# intf_conn_pwr.net
KiCad netlist of a schematic drawn in Altium Designer
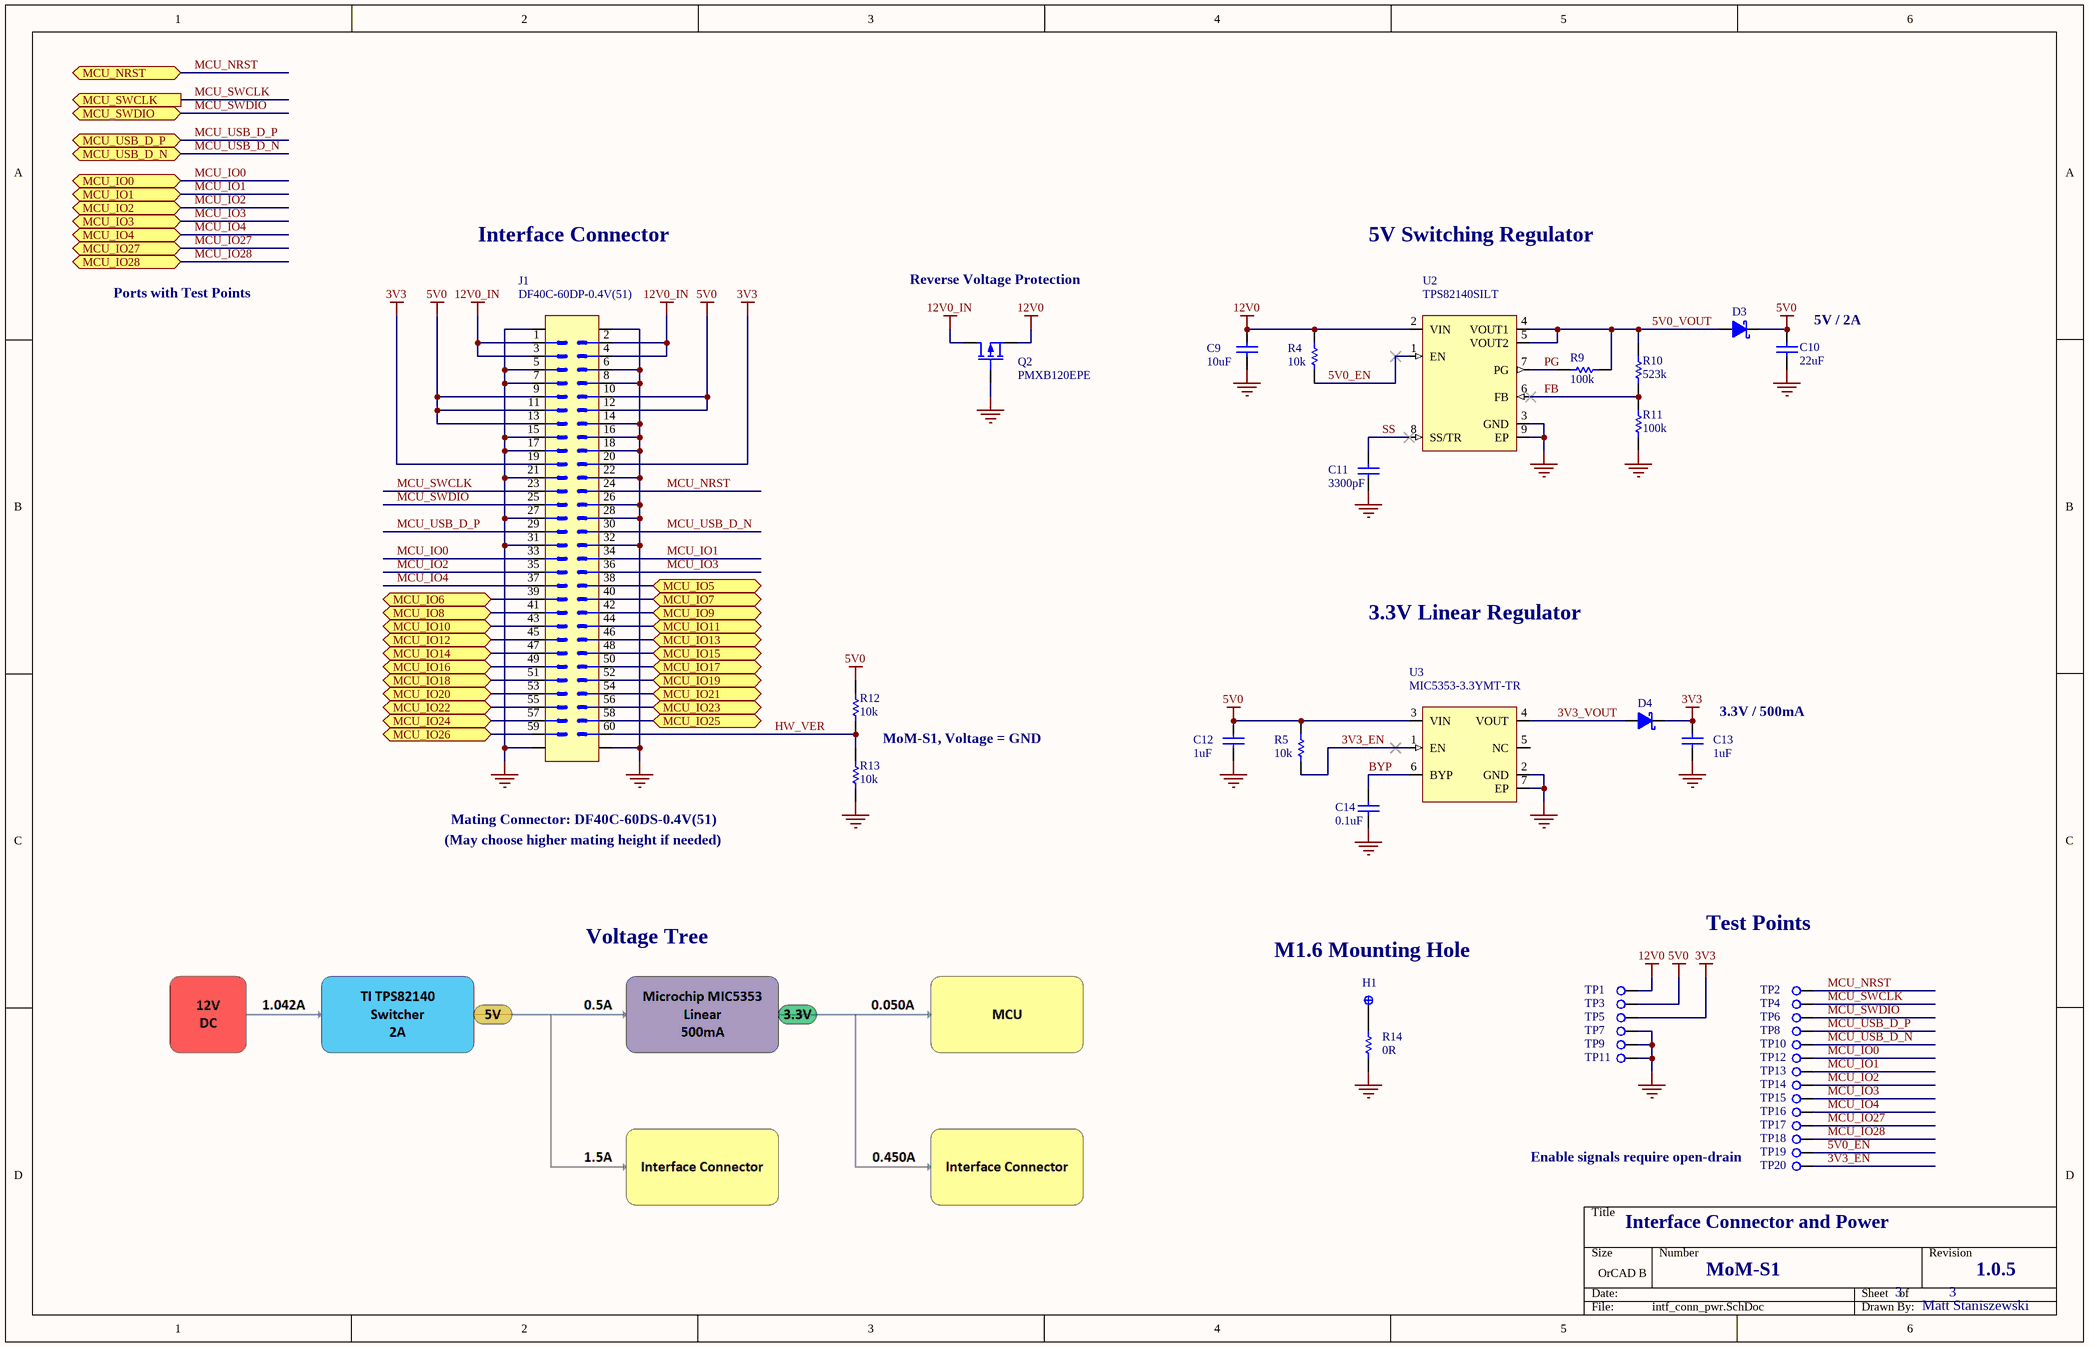
[diagram p0: intf_conn_pwr.SchDoc]

(export (version "E")
  (design (tool "Eeschema 10.0.6"))
  (components
    (comp (ref "C9")
      (value "10uF")
      (footprint "C0603")
      (description "CAP CER 10UF 25V X5R 0603")
      (fields
        (field (name "MANUFACTURER") "Murata")
        (field (name "MANUFACTURER PART NUMBER") "GRM188R61E106MA73D")
      )
      (libsource (lib "Capacitors") (part "10uF 25V 0603"))
    )
    (comp (ref "C10")
      (value "22uF")
      (footprint "C0603")
      (description "CAP CER 22UF 16V X5R 0603")
      (fields
        (field (name "MANUFACTURER") "Samsung")
        (field (name "MANUFACTURER PART NUMBER") "CL10A226MO7JZNC")
      )
      (libsource (lib "Capacitors") (part "22uF 16V 0603"))
    )
    (comp (ref "C11")
      (value "3300pF")
      (footprint "C0201")
      (description "CAP CER 3300PF 16V X7R 0201")
      (fields
        (field (name "MANUFACTURER") "Murata")
        (field (name "MANUFACTURER PART NUMBER") "GRM033R71C332KA88D")
      )
      (libsource (lib "Capacitors") (part "3300pF 16V 0201"))
    )
    (comp (ref "C12")
      (value "1uF")
      (footprint "C0402")
      (description "CAP CER 1UF 25V X5R 0402")
      (fields
        (field (name "MANUFACTURER") "Taiyo Yuden")
        (field (name "MANUFACTURER PART NUMBER") "TMK105BJ105MV-F")
      )
      (libsource (lib "Capacitors") (part "1uF 25V 0402"))
    )
    (comp (ref "C13")
      (value "1uF")
      (footprint "C0402")
      (description "CAP CER 1UF 25V X5R 0402")
      (fields
        (field (name "MANUFACTURER") "Taiyo Yuden")
        (field (name "MANUFACTURER PART NUMBER") "TMK105BJ105MV-F")
      )
      (libsource (lib "Capacitors") (part "1uF 25V 0402"))
    )
    (comp (ref "C14")
      (value "0.1uF")
      (footprint "C0201")
      (description "CAP CER 0.1UF 16V X5R 0201")
      (fields
        (field (name "MANUFACTURER") "Murata")
        (field (name "MANUFACTURER PART NUMBER") "GRM033R61C104ME84D")
      )
      (libsource (lib "Capacitors") (part "0.1uF 16V 0201"))
    )
    (comp (ref "D3")
      (value "SDM2U30CSP-7")
      (footprint "DIO_X3-WLB1608-2")
      (description "DIODE SCHTKY 30V 2A X3-WLB1608-2")
      (fields (field (name "MANUFACTURER") "Diodes"))
      (libsource (lib "Diodes") (part "SDM2U30CSP-7"))
    )
    (comp (ref "D4")
      (value "SDM2U30CSP-7")
      (footprint "DIO_X3-WLB1608-2")
      (description "DIODE SCHTKY 30V 2A X3-WLB1608-2")
      (fields (field (name "MANUFACTURER") "Diodes"))
      (libsource (lib "Diodes") (part "SDM2U30CSP-7"))
    )
    (comp (ref "H1")
      (value "M1.6 MNT HOLE")
      (footprint "MNT_HOLE_M1.6")
      (description "M1.6 Mounting Hole")
      (libsource (lib "Misc") (part "M1.6 MNT HOLE"))
    )
    (comp (ref "J1")
      (value "DF40C-60DP-0.4V(51)")
      (footprint "HRS_DF40C_60P_PLG")
      (description "CONN HDR 60POS 0.4MM SMD GOLD")
      (fields (field (name "MANUFACTURER") "Hirose"))
      (libsource (lib "Connectors") (part "60P 0.4mm Hirose Conn Plug"))
    )
    (comp (ref "Q2")
      (value "PMXB120EPE")
      (footprint "NXP_DFN1010D-3")
      (description "MOSFET P-CH 30V 2.4A 3DFN")
      (fields (field (name "MANUFACTURER") "NXP Semiconductors"))
      (libsource (lib "ICs") (part "PMXB120EPE"))
    )
    (comp (ref "R4")
      (value "10k")
      (footprint "R0201")
      (description "RES SMD 10K OHM 1% 1/20W 0201")
      (fields
        (field (name "MANUFACTURER") "Panasonic ECG")
        (field (name "MANUFACTURER PART NUMBER") "ERJ-1GEF1002C")
      )
      (libsource (lib "Resistors") (part "10k 0201"))
    )
    (comp (ref "R5")
      (value "10k")
      (footprint "R0201")
      (description "RES SMD 10K OHM 1% 1/20W 0201")
      (fields
        (field (name "MANUFACTURER") "Panasonic ECG")
        (field (name "MANUFACTURER PART NUMBER") "ERJ-1GEF1002C")
      )
      (libsource (lib "Resistors") (part "10k 0201"))
    )
    (comp (ref "R9")
      (value "100k")
      (footprint "R0201")
      (description "RES SMD 100K OHM 1% 1/20W 0201")
      (fields
        (field (name "MANUFACTURER") "Panasonic ECG")
        (field (name "MANUFACTURER PART NUMBER") "ERJ-1GEF1003C")
      )
      (libsource (lib "Resistors") (part "100k 0201"))
    )
    (comp (ref "R10")
      (value "523k")
      (footprint "R0201")
      (description "RES SMD 523K OHM 1% 1/20W 0201")
      (fields
        (field (name "MANUFACTURER") "Panasonic ECG")
        (field (name "MANUFACTURER PART NUMBER") "ERJ-1GEF5233C")
      )
      (libsource (lib "Resistors") (part "523k 0201"))
    )
    (comp (ref "R11")
      (value "100k")
      (footprint "R0201")
      (description "RES SMD 100K OHM 1% 1/20W 0201")
      (fields
        (field (name "MANUFACTURER") "Panasonic ECG")
        (field (name "MANUFACTURER PART NUMBER") "ERJ-1GEF1003C")
      )
      (libsource (lib "Resistors") (part "100k 0201"))
    )
    (comp (ref "R12")
      (value "10k")
      (footprint "R0201")
      (description "RES SMD 10K OHM 1% 1/20W 0201")
      (fields
        (field (name "MANUFACTURER") "Panasonic ECG")
        (field (name "MANUFACTURER PART NUMBER") "ERJ-1GEF1002C")
      )
      (libsource (lib "Resistors") (part "10k 0201"))
    )
    (comp (ref "R13")
      (value "10k")
      (footprint "R0201")
      (description "RES SMD 10K OHM 1% 1/20W 0201")
      (fields
        (field (name "MANUFACTURER") "Panasonic ECG")
        (field (name "MANUFACTURER PART NUMBER") "ERJ-1GEF1002C")
      )
      (libsource (lib "Resistors") (part "10k 0201"))
    )
    (comp (ref "R14")
      (value "0R")
      (footprint "R0201")
      (description "RES SMD 0 OHM JUMPER 1/20W 0201")
      (fields
        (field (name "MANUFACTURER") "Panasonic")
        (field (name "MANUFACTURER PART NUMBER") "ERJ-1GN0R00C")
      )
      (libsource (lib "Resistors") (part "0R 0201"))
    )
    (comp (ref "TP1")
      (value "TP SMT 0.5MM")
      (footprint "TP_SMT_0.5MM")
      (description "0.5mm SMT Test Point")
      (libsource (lib "Misc") (part "TP SMT 0.5MM"))
    )
    (comp (ref "TP2")
      (value "TP SMT 0.5MM")
      (footprint "TP_SMT_0.5MM")
      (description "0.5mm SMT Test Point")
      (libsource (lib "Misc") (part "TP SMT 0.5MM"))
    )
    (comp (ref "TP3")
      (value "TP SMT 0.5MM")
      (footprint "TP_SMT_0.5MM")
      (description "0.5mm SMT Test Point")
      (libsource (lib "Misc") (part "TP SMT 0.5MM"))
    )
    (comp (ref "TP4")
      (value "TP SMT 0.5MM")
      (footprint "TP_SMT_0.5MM")
      (description "0.5mm SMT Test Point")
      (libsource (lib "Misc") (part "TP SMT 0.5MM"))
    )
    (comp (ref "TP5")
      (value "TP SMT 0.5MM")
      (footprint "TP_SMT_0.5MM")
      (description "0.5mm SMT Test Point")
      (libsource (lib "Misc") (part "TP SMT 0.5MM"))
    )
    (comp (ref "TP6")
      (value "TP SMT 0.5MM")
      (footprint "TP_SMT_0.5MM")
      (description "0.5mm SMT Test Point")
      (libsource (lib "Misc") (part "TP SMT 0.5MM"))
    )
    (comp (ref "TP7")
      (value "TP SMT 0.5MM")
      (footprint "TP_SMT_0.5MM")
      (description "0.5mm SMT Test Point")
      (libsource (lib "Misc") (part "TP SMT 0.5MM"))
    )
    (comp (ref "TP8")
      (value "TP SMT 0.5MM")
      (footprint "TP_SMT_0.5MM")
      (description "0.5mm SMT Test Point")
      (libsource (lib "Misc") (part "TP SMT 0.5MM"))
    )
    (comp (ref "TP9")
      (value "TP SMT 0.5MM")
      (footprint "TP_SMT_0.5MM")
      (description "0.5mm SMT Test Point")
      (libsource (lib "Misc") (part "TP SMT 0.5MM"))
    )
    (comp (ref "TP10")
      (value "TP SMT 0.5MM")
      (footprint "TP_SMT_0.5MM")
      (description "0.5mm SMT Test Point")
      (libsource (lib "Misc") (part "TP SMT 0.5MM"))
    )
    (comp (ref "TP11")
      (value "TP SMT 0.5MM")
      (footprint "TP_SMT_0.5MM")
      (description "0.5mm SMT Test Point")
      (libsource (lib "Misc") (part "TP SMT 0.5MM"))
    )
    (comp (ref "TP12")
      (value "TP SMT 0.5MM")
      (footprint "TP_SMT_0.5MM")
      (description "0.5mm SMT Test Point")
      (libsource (lib "Misc") (part "TP SMT 0.5MM"))
    )
    (comp (ref "TP13")
      (value "TP SMT 0.5MM")
      (footprint "TP_SMT_0.5MM")
      (description "0.5mm SMT Test Point")
      (libsource (lib "Misc") (part "TP SMT 0.5MM"))
    )
    (comp (ref "TP14")
      (value "TP SMT 0.5MM")
      (footprint "TP_SMT_0.5MM")
      (description "0.5mm SMT Test Point")
      (libsource (lib "Misc") (part "TP SMT 0.5MM"))
    )
    (comp (ref "TP15")
      (value "TP SMT 0.5MM")
      (footprint "TP_SMT_0.5MM")
      (description "0.5mm SMT Test Point")
      (libsource (lib "Misc") (part "TP SMT 0.5MM"))
    )
    (comp (ref "TP16")
      (value "TP SMT 0.5MM")
      (footprint "TP_SMT_0.5MM")
      (description "0.5mm SMT Test Point")
      (libsource (lib "Misc") (part "TP SMT 0.5MM"))
    )
    (comp (ref "TP17")
      (value "TP SMT 0.5MM")
      (footprint "TP_SMT_0.5MM")
      (description "0.5mm SMT Test Point")
      (libsource (lib "Misc") (part "TP SMT 0.5MM"))
    )
    (comp (ref "TP18")
      (value "TP SMT 0.5MM")
      (footprint "TP_SMT_0.5MM")
      (description "0.5mm SMT Test Point")
      (libsource (lib "Misc") (part "TP SMT 0.5MM"))
    )
    (comp (ref "TP19")
      (value "TP SMT 0.5MM")
      (footprint "TP_SMT_0.5MM")
      (description "0.5mm SMT Test Point")
      (libsource (lib "Misc") (part "TP SMT 0.5MM"))
    )
    (comp (ref "TP20")
      (value "TP SMT 0.5MM")
      (footprint "TP_SMT_0.5MM")
      (description "0.5mm SMT Test Point")
      (libsource (lib "Misc") (part "TP SMT 0.5MM"))
    )
    (comp (ref "U2")
      (value "TPS82140SILT")
      (footprint "TI_USIL8_SIL0008D")
      (description "STEP-DOWN CONVERTER MICROSIP")
      (fields (field (name "MANUFACTURER") "Texas Instruments"))
      (libsource (lib "ICs") (part "TPS82140SILT"))
    )
    (comp (ref "U3")
      (value "MIC5353-3.3YMT-TR")
      (footprint "MCP_MLF6_MT")
      (description "IC REG LINEAR 3.3V 500MA 6TMLF")
      (fields (field (name "MANUFACTURER") "Microchip"))
      (libsource (lib "ICs") (part "MIC5353-3.3YMT-TR"))
    )
  )
  (nets
    (net (code "1") (name "/3V3_EN") (class "Default")
      (node (ref "R5") (pin "1") (pinfunction "1_1") (pintype "passive"))
      (node (ref "TP20") (pin "1") (pinfunction "1_1") (pintype "passive"))
      (node (ref "U3") (pin "1") (pinfunction "EN_1") (pintype "input"))
    )
    (net (code "2") (name "/3V3_VOUT") (class "Default")
      (node (ref "D4") (pin "2") (pinfunction "A_2") (pintype "passive"))
      (node (ref "U3") (pin "4") (pinfunction "VOUT_4") (pintype "power_in"))
    )
    (net (code "3") (name "/5V0_EN") (class "Default")
      (node (ref "R4") (pin "1") (pinfunction "1_1") (pintype "passive"))
      (node (ref "TP19") (pin "1") (pinfunction "1_1") (pintype "passive"))
      (node (ref "U2") (pin "1") (pinfunction "EN_1") (pintype "input"))
    )
    (net (code "4") (name "/5V0_VOUT") (class "Default")
      (node (ref "D3") (pin "2") (pinfunction "A_2") (pintype "passive"))
      (node (ref "R10") (pin "2") (pinfunction "2_2") (pintype "passive"))
      (node (ref "R9") (pin "2") (pinfunction "2_2") (pintype "passive"))
      (node (ref "U2") (pin "4") (pinfunction "VOUT1_4") (pintype "power_in"))
      (node (ref "U2") (pin "5") (pinfunction "VOUT2_5") (pintype "power_in"))
    )
    (net (code "5") (name "/BYP") (class "Default")
      (node (ref "C14") (pin "2") (pinfunction "2_2") (pintype "passive"))
      (node (ref "U3") (pin "6") (pinfunction "BYP_6") (pintype "power_in"))
    )
    (net (code "6") (name "/FB") (class "Default")
      (node (ref "R10") (pin "1") (pinfunction "1_1") (pintype "passive"))
      (node (ref "R11") (pin "2") (pinfunction "2_2") (pintype "passive"))
      (node (ref "U2") (pin "6") (pinfunction "FB_6") (pintype "input"))
    )
    (net (code "7") (name "/HW_VER") (class "Default")
      (node (ref "J1") (pin "60") (pinfunction "60_60") (pintype "passive"))
      (node (ref "R12") (pin "1") (pinfunction "1_1") (pintype "passive"))
      (node (ref "R13") (pin "2") (pinfunction "2_2") (pintype "passive"))
    )
    (net (code "8") (name "/MCU_IO0") (class "Default")
      (node (ref "J1") (pin "33") (pinfunction "33_33") (pintype "passive"))
      (node (ref "TP12") (pin "1") (pinfunction "1_1") (pintype "passive"))
    )
    (net (code "9") (name "/MCU_IO1") (class "Default")
      (node (ref "J1") (pin "34") (pinfunction "34_34") (pintype "passive"))
      (node (ref "TP13") (pin "1") (pinfunction "1_1") (pintype "passive"))
    )
    (net (code "10") (name "/MCU_IO2") (class "Default")
      (node (ref "J1") (pin "35") (pinfunction "35_35") (pintype "passive"))
      (node (ref "TP14") (pin "1") (pinfunction "1_1") (pintype "passive"))
    )
    (net (code "11") (name "/MCU_IO3") (class "Default")
      (node (ref "J1") (pin "36") (pinfunction "36_36") (pintype "passive"))
      (node (ref "TP15") (pin "1") (pinfunction "1_1") (pintype "passive"))
    )
    (net (code "12") (name "/MCU_IO4") (class "Default")
      (node (ref "J1") (pin "37") (pinfunction "37_37") (pintype "passive"))
      (node (ref "TP16") (pin "1") (pinfunction "1_1") (pintype "passive"))
    )
    (net (code "13") (name "/MCU_IO5") (class "Default")
      (node (ref "J1") (pin "38") (pinfunction "38_38") (pintype "passive"))
    )
    (net (code "14") (name "/MCU_IO6") (class "Default")
      (node (ref "J1") (pin "39") (pinfunction "39_39") (pintype "passive"))
    )
    (net (code "15") (name "/MCU_IO7") (class "Default")
      (node (ref "J1") (pin "40") (pinfunction "40_40") (pintype "passive"))
    )
    (net (code "16") (name "/MCU_IO8") (class "Default")
      (node (ref "J1") (pin "41") (pinfunction "41_41") (pintype "passive"))
    )
    (net (code "17") (name "/MCU_IO9") (class "Default")
      (node (ref "J1") (pin "42") (pinfunction "42_42") (pintype "passive"))
    )
    (net (code "18") (name "/MCU_IO10") (class "Default")
      (node (ref "J1") (pin "43") (pinfunction "43_43") (pintype "passive"))
    )
    (net (code "19") (name "/MCU_IO11") (class "Default")
      (node (ref "J1") (pin "44") (pinfunction "44_44") (pintype "passive"))
    )
    (net (code "20") (name "/MCU_IO12") (class "Default")
      (node (ref "J1") (pin "45") (pinfunction "45_45") (pintype "passive"))
    )
    (net (code "21") (name "/MCU_IO13") (class "Default")
      (node (ref "J1") (pin "46") (pinfunction "46_46") (pintype "passive"))
    )
    (net (code "22") (name "/MCU_IO14") (class "Default")
      (node (ref "J1") (pin "47") (pinfunction "47_47") (pintype "passive"))
    )
    (net (code "23") (name "/MCU_IO15") (class "Default")
      (node (ref "J1") (pin "48") (pinfunction "48_48") (pintype "passive"))
    )
    (net (code "24") (name "/MCU_IO16") (class "Default")
      (node (ref "J1") (pin "49") (pinfunction "49_49") (pintype "passive"))
    )
    (net (code "25") (name "/MCU_IO17") (class "Default")
      (node (ref "J1") (pin "50") (pinfunction "50_50") (pintype "passive"))
    )
    (net (code "26") (name "/MCU_IO18") (class "Default")
      (node (ref "J1") (pin "51") (pinfunction "51_51") (pintype "passive"))
    )
    (net (code "27") (name "/MCU_IO19") (class "Default")
      (node (ref "J1") (pin "52") (pinfunction "52_52") (pintype "passive"))
    )
    (net (code "28") (name "/MCU_IO20") (class "Default")
      (node (ref "J1") (pin "53") (pinfunction "53_53") (pintype "passive"))
    )
    (net (code "29") (name "/MCU_IO21") (class "Default")
      (node (ref "J1") (pin "54") (pinfunction "54_54") (pintype "passive"))
    )
    (net (code "30") (name "/MCU_IO22") (class "Default")
      (node (ref "J1") (pin "55") (pinfunction "55_55") (pintype "passive"))
    )
    (net (code "31") (name "/MCU_IO23") (class "Default")
      (node (ref "J1") (pin "56") (pinfunction "56_56") (pintype "passive"))
    )
    (net (code "32") (name "/MCU_IO24") (class "Default")
      (node (ref "J1") (pin "57") (pinfunction "57_57") (pintype "passive"))
    )
    (net (code "33") (name "/MCU_IO25") (class "Default")
      (node (ref "J1") (pin "58") (pinfunction "58_58") (pintype "passive"))
    )
    (net (code "34") (name "/MCU_IO26") (class "Default")
      (node (ref "J1") (pin "59") (pinfunction "59_59") (pintype "passive"))
    )
    (net (code "35") (name "/MCU_IO27") (class "Default")
      (node (ref "TP17") (pin "1") (pinfunction "1_1") (pintype "passive"))
    )
    (net (code "36") (name "/MCU_IO28") (class "Default")
      (node (ref "TP18") (pin "1") (pinfunction "1_1") (pintype "passive"))
    )
    (net (code "37") (name "/MCU_NRST") (class "Default")
      (node (ref "J1") (pin "24") (pinfunction "24_24") (pintype "passive"))
      (node (ref "TP2") (pin "1") (pinfunction "1_1") (pintype "passive"))
    )
    (net (code "38") (name "/MCU_SWCLK") (class "Default")
      (node (ref "J1") (pin "23") (pinfunction "23_23") (pintype "passive"))
      (node (ref "TP4") (pin "1") (pinfunction "1_1") (pintype "passive"))
    )
    (net (code "39") (name "/MCU_SWDIO") (class "Default")
      (node (ref "J1") (pin "25") (pinfunction "25_25") (pintype "passive"))
      (node (ref "TP6") (pin "1") (pinfunction "1_1") (pintype "passive"))
    )
    (net (code "40") (name "/MCU_USB_D_N") (class "Default")
      (node (ref "J1") (pin "30") (pinfunction "30_30") (pintype "passive"))
      (node (ref "TP10") (pin "1") (pinfunction "1_1") (pintype "passive"))
    )
    (net (code "41") (name "/MCU_USB_D_P") (class "Default")
      (node (ref "J1") (pin "29") (pinfunction "29_29") (pintype "passive"))
      (node (ref "TP8") (pin "1") (pinfunction "1_1") (pintype "passive"))
    )
    (net (code "42") (name "/PG") (class "Default")
      (node (ref "R9") (pin "1") (pinfunction "1_1") (pintype "passive"))
      (node (ref "U2") (pin "7") (pinfunction "PG_7") (pintype "output"))
    )
    (net (code "43") (name "/SS") (class "Default")
      (node (ref "C11") (pin "2") (pinfunction "2_2") (pintype "passive"))
      (node (ref "U2") (pin "8") (pinfunction "SS/TR_8") (pintype "input"))
    )
    (net (code "44") (name "3V3") (class "Default")
      (node (ref "C13") (pin "2") (pinfunction "2_2") (pintype "passive"))
      (node (ref "D4") (pin "1") (pinfunction "K_1") (pintype "passive"))
      (node (ref "J1") (pin "19") (pinfunction "19_19") (pintype "passive"))
      (node (ref "J1") (pin "20") (pinfunction "20_20") (pintype "passive"))
      (node (ref "TP5") (pin "1") (pinfunction "1_1") (pintype "passive"))
    )
    (net (code "45") (name "5V0") (class "Default")
      (node (ref "C10") (pin "2") (pinfunction "2_2") (pintype "passive"))
      (node (ref "C12") (pin "2") (pinfunction "2_2") (pintype "passive"))
      (node (ref "D3") (pin "1") (pinfunction "K_1") (pintype "passive"))
      (node (ref "J1") (pin "10") (pinfunction "10_10") (pintype "passive"))
      (node (ref "J1") (pin "11") (pinfunction "11_11") (pintype "passive"))
      (node (ref "J1") (pin "12") (pinfunction "12_12") (pintype "passive"))
      (node (ref "J1") (pin "13") (pinfunction "13_13") (pintype "passive"))
      (node (ref "J1") (pin "9") (pinfunction "9_9") (pintype "passive"))
      (node (ref "R12") (pin "2") (pinfunction "2_2") (pintype "passive"))
      (node (ref "R5") (pin "2") (pinfunction "2_2") (pintype "passive"))
      (node (ref "TP3") (pin "1") (pinfunction "1_1") (pintype "passive"))
      (node (ref "U3") (pin "3") (pinfunction "VIN_3") (pintype "power_in"))
    )
    (net (code "46") (name "12V0") (class "Default")
      (node (ref "C9") (pin "2") (pinfunction "2_2") (pintype "passive"))
      (node (ref "Q2") (pin "2") (pinfunction "S_2") (pintype "passive"))
      (node (ref "R4") (pin "2") (pinfunction "2_2") (pintype "passive"))
      (node (ref "TP1") (pin "1") (pinfunction "1_1") (pintype "passive"))
      (node (ref "U2") (pin "2") (pinfunction "VIN_2") (pintype "power_in"))
    )
    (net (code "47") (name "12V0_IN") (class "Default")
      (node (ref "J1") (pin "1") (pinfunction "1_1") (pintype "passive"))
      (node (ref "J1") (pin "2") (pinfunction "2_2") (pintype "passive"))
      (node (ref "J1") (pin "3") (pinfunction "3_3") (pintype "passive"))
      (node (ref "J1") (pin "4") (pinfunction "4_4") (pintype "passive"))
      (node (ref "Q2") (pin "3") (pinfunction "D_3") (pintype "passive"))
    )
    (net (code "48") (name "GND") (class "Default")
      (node (ref "C10") (pin "1") (pinfunction "1_1") (pintype "passive"))
      (node (ref "C11") (pin "1") (pinfunction "1_1") (pintype "passive"))
      (node (ref "C12") (pin "1") (pinfunction "1_1") (pintype "passive"))
      (node (ref "C13") (pin "1") (pinfunction "1_1") (pintype "passive"))
      (node (ref "C14") (pin "1") (pinfunction "1_1") (pintype "passive"))
      (node (ref "C9") (pin "1") (pinfunction "1_1") (pintype "passive"))
      (node (ref "J1") (pin "14") (pinfunction "14_14") (pintype "passive"))
      (node (ref "J1") (pin "15") (pinfunction "15_15") (pintype "passive"))
      (node (ref "J1") (pin "16") (pinfunction "16_16") (pintype "passive"))
      (node (ref "J1") (pin "17") (pinfunction "17_17") (pintype "passive"))
      (node (ref "J1") (pin "18") (pinfunction "18_18") (pintype "passive"))
      (node (ref "J1") (pin "21") (pinfunction "21_21") (pintype "passive"))
      (node (ref "J1") (pin "22") (pinfunction "22_22") (pintype "passive"))
      (node (ref "J1") (pin "26") (pinfunction "26_26") (pintype "passive"))
      (node (ref "J1") (pin "27") (pinfunction "27_27") (pintype "passive"))
      (node (ref "J1") (pin "28") (pinfunction "28_28") (pintype "passive"))
      (node (ref "J1") (pin "31") (pinfunction "31_31") (pintype "passive"))
      (node (ref "J1") (pin "32") (pinfunction "32_32") (pintype "passive"))
      (node (ref "J1") (pin "5") (pinfunction "5_5") (pintype "passive"))
      (node (ref "J1") (pin "6") (pinfunction "6_6") (pintype "passive"))
      (node (ref "J1") (pin "61") (pinfunction "61_61") (pintype "passive"))
      (node (ref "J1") (pin "62") (pinfunction "62_62") (pintype "passive"))
      (node (ref "J1") (pin "63") (pinfunction "63_63") (pintype "passive"))
      (node (ref "J1") (pin "64") (pinfunction "64_64") (pintype "passive"))
      (node (ref "J1") (pin "7") (pinfunction "7_7") (pintype "passive"))
      (node (ref "J1") (pin "8") (pinfunction "8_8") (pintype "passive"))
      (node (ref "Q2") (pin "1") (pinfunction "G_1") (pintype "passive"))
      (node (ref "R11") (pin "1") (pinfunction "1_1") (pintype "passive"))
      (node (ref "R13") (pin "1") (pinfunction "1_1") (pintype "passive"))
      (node (ref "R14") (pin "1") (pinfunction "1_1") (pintype "passive"))
      (node (ref "TP11") (pin "1") (pinfunction "1_1") (pintype "passive"))
      (node (ref "TP7") (pin "1") (pinfunction "1_1") (pintype "passive"))
      (node (ref "TP9") (pin "1") (pinfunction "1_1") (pintype "passive"))
      (node (ref "U2") (pin "3") (pinfunction "GND_3") (pintype "power_in"))
      (node (ref "U2") (pin "9") (pinfunction "EP_9") (pintype "power_in"))
      (node (ref "U3") (pin "2") (pinfunction "GND_2") (pintype "power_in"))
      (node (ref "U3") (pin "7") (pinfunction "EP_7") (pintype "power_in"))
    )
    (net (code "49") (name "Net-(H1-Pad1)") (class "Default")
      (node (ref "H1") (pin "1") (pinfunction "1_1") (pintype "passive"))
      (node (ref "R14") (pin "2") (pinfunction "2_2") (pintype "passive"))
    )
    (net (code "50") (name "unconnected-(U3-NC-Pad5)") (class "Default")
      (node (ref "U3") (pin "5") (pinfunction "NC_5") (pintype "passive"))
    )
  )
)
